# mainPCB.net
KiCad netlist of a schematic drawn in EAGLE
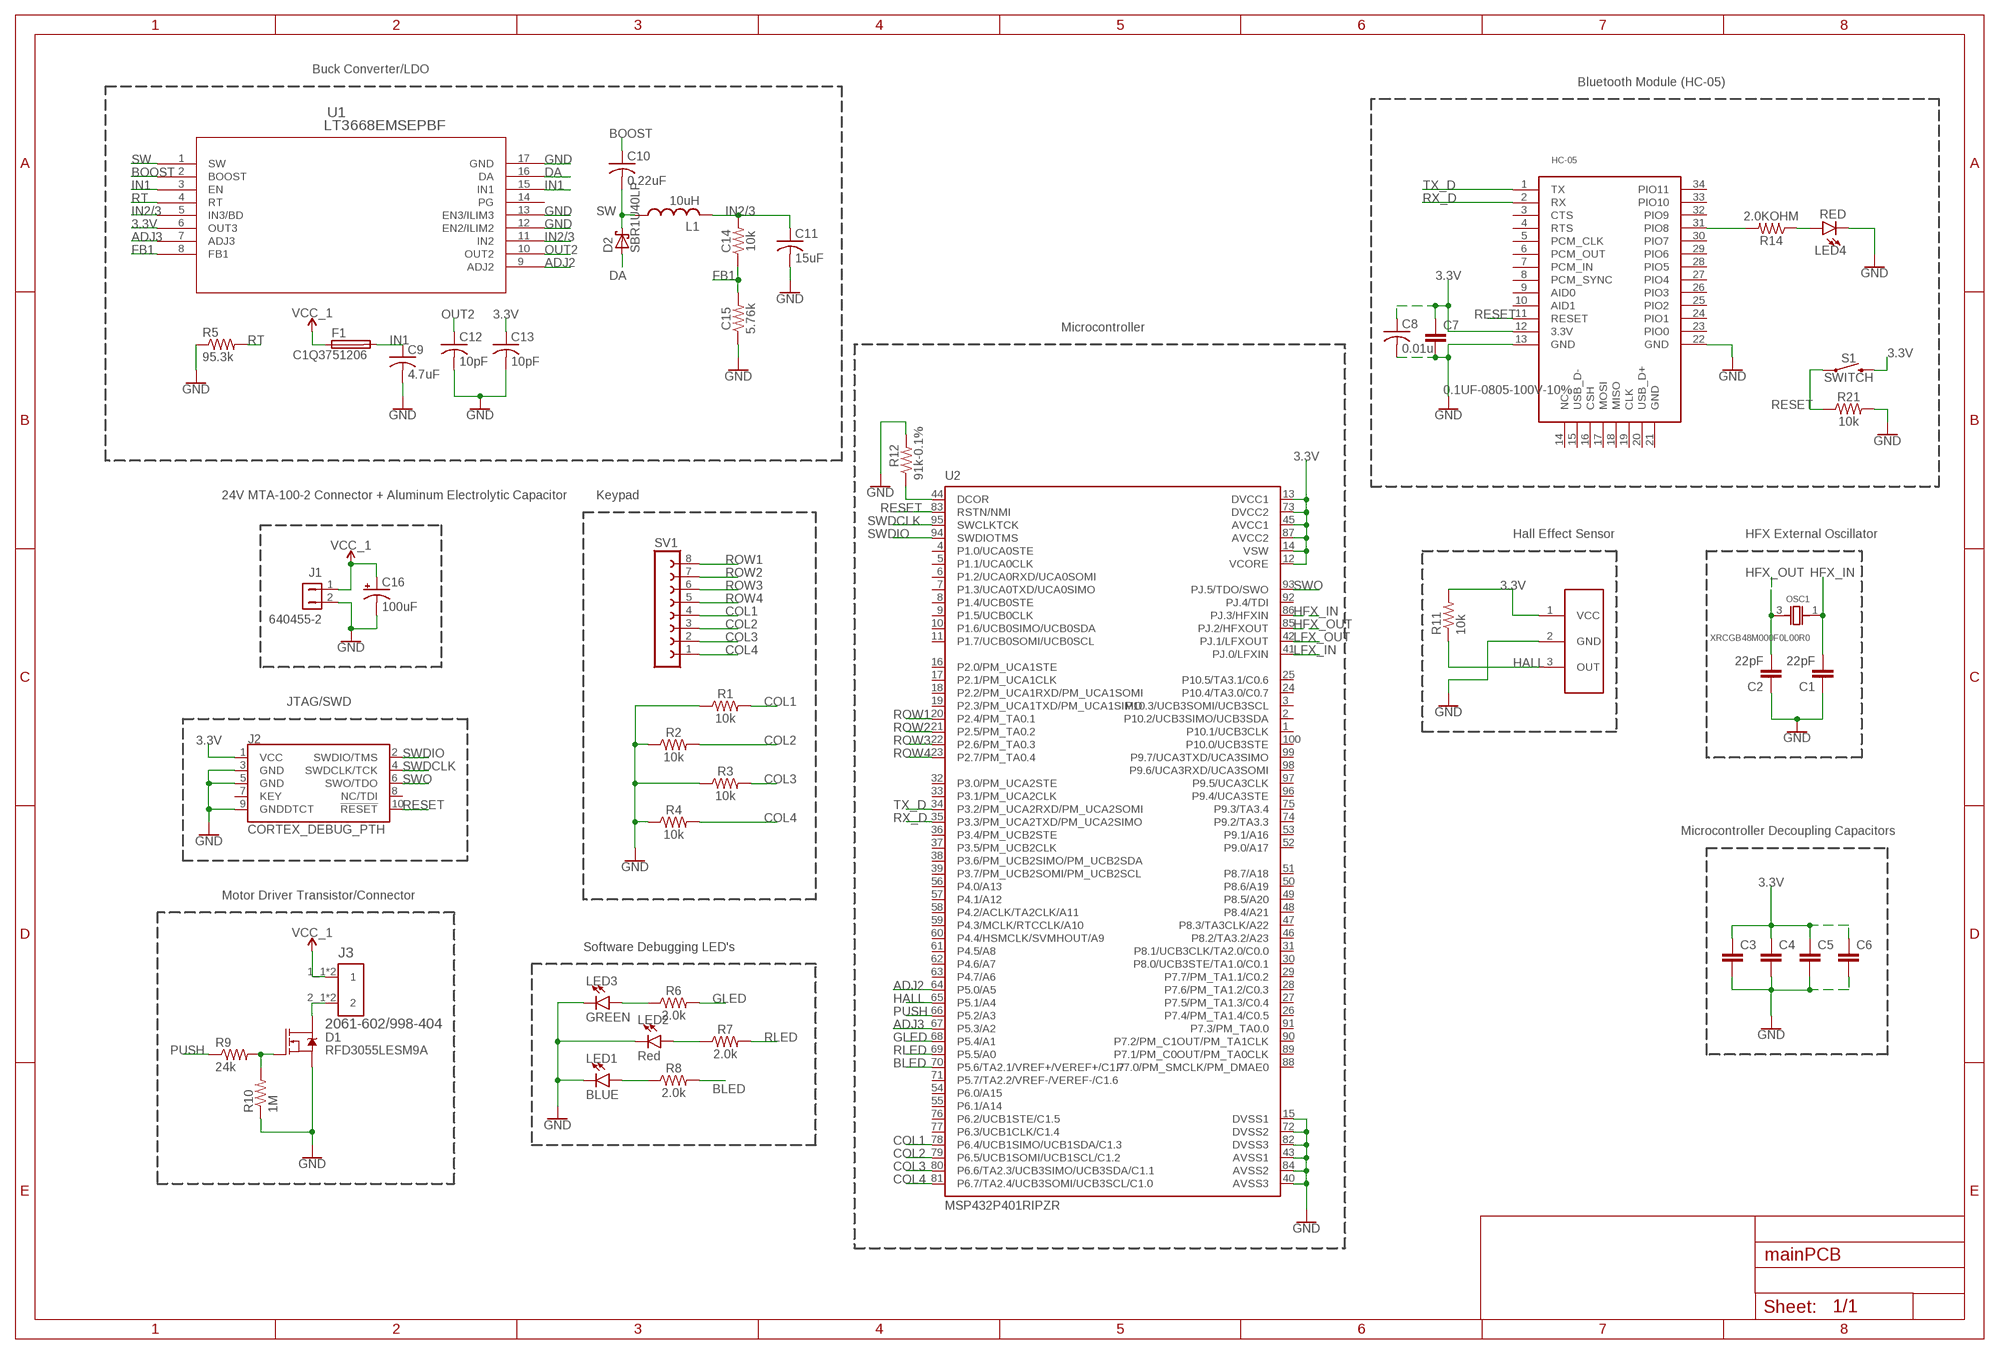
[diagram p0: schematic, sheet 1]

(export (version "E")
  (design (tool "Eeschema 10.0.6"))
  (components
    (comp (ref "C1")
      (value "22pF")
      (footprint "eagle-import:0603")
      (libsource (lib "eagle-import") (part "22PF-0603-50V-5%"))
    )
    (comp (ref "C2")
      (value "22pF")
      (footprint "eagle-import:0603")
      (libsource (lib "eagle-import") (part "22PF-0603-50V-5%"))
    )
    (comp (ref "C3")
      (value "0.1UF-0805-100V-10%")
      (footprint "eagle-import:0805")
      (libsource (lib "eagle-import") (part "0.1UF-0805-100V-10%"))
    )
    (comp (ref "C4")
      (value "0.1UF-0805-100V-10%")
      (footprint "eagle-import:0805")
      (libsource (lib "eagle-import") (part "0.1UF-0805-100V-10%"))
    )
    (comp (ref "C5")
      (value "0.1UF-0805-100V-10%")
      (footprint "eagle-import:0805")
      (libsource (lib "eagle-import") (part "0.1UF-0805-100V-10%"))
    )
    (comp (ref "C6")
      (value "0.1UF-0805-100V-10%")
      (footprint "eagle-import:0805")
      (libsource (lib "eagle-import") (part "0.1UF-0805-100V-10%"))
    )
    (comp (ref "C7")
      (value "0.1UF-0805-100V-10%")
      (footprint "eagle-import:0805")
      (libsource (lib "eagle-import") (part "0.1UF-0805-100V-10%"))
    )
    (comp (ref "C8")
      (value "0.01u")
      (footprint "eagle-import:C0805")
      (libsource (lib "eagle-import") (part "C-USC0805"))
    )
    (comp (ref "C9")
      (value "4.7uF")
      (footprint "eagle-import:C0805")
      (libsource (lib "eagle-import") (part "C-USC0805"))
    )
    (comp (ref "C10")
      (value "0.22uF")
      (footprint "eagle-import:C0805")
      (libsource (lib "eagle-import") (part "C-USC0805"))
    )
    (comp (ref "C11")
      (value "15uF")
      (footprint "eagle-import:C0805")
      (libsource (lib "eagle-import") (part "C-USC0805"))
    )
    (comp (ref "C12")
      (value "10pF")
      (footprint "eagle-import:C0805")
      (libsource (lib "eagle-import") (part "C-USC0805"))
    )
    (comp (ref "C13")
      (value "10pF")
      (footprint "eagle-import:C0805")
      (libsource (lib "eagle-import") (part "C-USC0805"))
    )
    (comp (ref "C14")
      (value "10k")
      (footprint "eagle-import:R0805")
      (libsource (lib "eagle-import") (part "ERJ-PB6"))
    )
    (comp (ref "C15")
      (value "5.76k")
      (footprint "eagle-import:R0805")
      (libsource (lib "eagle-import") (part "ERJ-PB6"))
    )
    (comp (ref "C16")
      (value "100uF")
      (footprint "eagle-import:PANASONIC_D")
      (libsource (lib "eagle-import") (part "EEE-1HA101UP"))
    )
    (comp (ref "D1")
      (value "RFD3055LESM9A")
      (footprint "eagle-import:DPAK229P990X239-4N")
      (libsource (lib "eagle-import") (part "RFD3055LESM9A"))
    )
    (comp (ref "D2")
      (value "SBR1U40LP")
      (footprint "eagle-import:3-XDFN")
      (libsource (lib "eagle-import") (part "SBR1U40LP"))
    )
    (comp (ref "F1")
      (value "C1Q3751206")
      (footprint "eagle-import:C1206")
      (libsource (lib "eagle-import") (part "C1Q3751206"))
    )
    (comp (ref "H1")
      (value "HES")
      (footprint "eagle-import:SIP3-UA")
      (libsource (lib "eagle-import") (part "AH1807-P-B"))
    )
    (comp (ref "HC-05")
      (value "HC-05")
      (footprint "eagle-import:XCVR_HC-05")
      (libsource (lib "eagle-import") (part "HC-05HC-05"))
    )
    (comp (ref "J1")
      (value "640455-2")
      (footprint "eagle-import:2-PIN_CONNECTOR")
      (fields (field (name "MF") "TE Connectivity"))
      (libsource (lib "eagle-import") (part "640455-2"))
    )
    (comp (ref "J2")
      (value "CORTEX_DEBUG_PTH")
      (footprint "eagle-import:2X5-PTH-1.27MM")
      (libsource (lib "eagle-import") (part "CORTEX_DEBUG_PTH"))
    )
    (comp (ref "J3")
      (value "2061-602/998-404")
      (footprint "eagle-import:WAGO_2061-602_998-404")
      (fields (field (name "MF") "WAGO"))
      (libsource (lib "eagle-import") (part "2061-602/998-404"))
    )
    (comp (ref "L1")
      (value "10uH")
      (footprint "eagle-import:L3225M")
      (libsource (lib "eagle-import") (part "CBC3225T150KR1210"))
    )
    (comp (ref "LED1")
      (value "BLUE")
      (footprint "eagle-import:LED-0603")
      (libsource (lib "eagle-import") (part "LED-BLUE0603"))
    )
    (comp (ref "LED2")
      (value "Red")
      (footprint "eagle-import:LED-0603")
      (libsource (lib "eagle-import") (part "LED-RED0603-SMART"))
    )
    (comp (ref "LED3")
      (value "GREEN")
      (footprint "eagle-import:LED-0603")
      (libsource (lib "eagle-import") (part "LED-GREEN0603"))
    )
    (comp (ref "LED4")
      (value "RED")
      (footprint "eagle-import:LED-0603")
      (libsource (lib "eagle-import") (part "LED-RED0603"))
    )
    (comp (ref "OSC1")
      (value "XRCGB48M000F0L00R0")
      (footprint "eagle-import:XTAL_XRCGB24M000F0L00R0")
      (libsource (lib "eagle-import") (part "XRCGB48M000F0L00R0"))
    )
    (comp (ref "R1")
      (value "10k")
      (footprint "eagle-import:0805")
      (libsource (lib "eagle-import") (part "10KOHM-0805-1/4W-1%"))
    )
    (comp (ref "R2")
      (value "10k")
      (footprint "eagle-import:0805")
      (libsource (lib "eagle-import") (part "10KOHM-0805-1/4W-1%"))
    )
    (comp (ref "R3")
      (value "10k")
      (footprint "eagle-import:0805")
      (libsource (lib "eagle-import") (part "10KOHM-0805-1/4W-1%"))
    )
    (comp (ref "R4")
      (value "10k")
      (footprint "eagle-import:0805")
      (libsource (lib "eagle-import") (part "10KOHM-0805-1/4W-1%"))
    )
    (comp (ref "R5")
      (value "95.3k")
      (footprint "eagle-import:R0805")
      (libsource (lib "eagle-import") (part "R-US_R0805"))
    )
    (comp (ref "R6")
      (value "2.0k")
      (footprint "eagle-import:0603")
      (libsource (lib "eagle-import") (part "2.0KOHM-0603-1/10W-5%"))
    )
    (comp (ref "R7")
      (value "2.0k")
      (footprint "eagle-import:0603")
      (libsource (lib "eagle-import") (part "2.0KOHM-0603-1/10W-5%"))
    )
    (comp (ref "R8")
      (value "2.0k")
      (footprint "eagle-import:0603")
      (libsource (lib "eagle-import") (part "2.0KOHM-0603-1/10W-5%"))
    )
    (comp (ref "R9")
      (value "24k")
      (footprint "eagle-import:R0805")
      (libsource (lib "eagle-import") (part "R-US_R0805"))
    )
    (comp (ref "R10")
      (value "1M")
      (footprint "eagle-import:R0805")
      (libsource (lib "eagle-import") (part "R-US_R0805"))
    )
    (comp (ref "R11")
      (value "10k")
      (footprint "eagle-import:R0805")
      (libsource (lib "eagle-import") (part "R-US_R0805"))
    )
    (comp (ref "R12")
      (value "91k-0.1%")
      (footprint "eagle-import:R0805")
      (libsource (lib "eagle-import") (part "R-US_R0805"))
    )
    (comp (ref "R14")
      (value "2.0KOHM")
      (footprint "eagle-import:0805")
      (libsource (lib "eagle-import") (part "2.0KOHM"))
    )
    (comp (ref "R21")
      (value "10k")
      (footprint "eagle-import:0805")
      (libsource (lib "eagle-import") (part "10KOHM-0805-1/4W-1%"))
    )
    (comp (ref "S1")
      (value "SWITCH")
      (footprint "eagle-import:TACTILE_SWITCH_SMD_5.2MM")
      (libsource (lib "eagle-import") (part "MOMENTARY-SWITCH-SPST-SMD-5.2-REDUNDANT"))
    )
    (comp (ref "SV1")
      (value "FE08-1")
      (footprint "eagle-import:FE08")
      (libsource (lib "eagle-import") (part "FE08-1"))
    )
    (comp (ref "U1")
      (value "LT3668EMSEPBF")
      (footprint "eagle-import:MSOP-16_MSE")
      (fields
        (field (name "DIGI-KEY_PART_NUMBER") "LT3668EMSE#PBF-ND")
        (field (name "MF") "Linear Technology")
        (field (name "MP") "LT3668EMSE#PBF")
      )
      (libsource (lib "eagle-import") (part "LT3668EMSEPBF"))
    )
    (comp (ref "U2")
      (value "MSP432P401RIPZR")
      (footprint "eagle-import:QFP50P1600X1600X160-100N")
      (fields (field (name "MF") "Texas Instruments"))
      (libsource (lib "eagle-import") (part "MSP432P401RIPZR"))
    )
  )
  (nets
    (net (code "1") (name "/3.3V") (class "Default")
      (node (ref "C13") (pin "1") (pinfunction "1_1") (pintype "passive"))
      (node (ref "C3") (pin "1") (pinfunction "1_1") (pintype "passive"))
      (node (ref "C4") (pin "1") (pinfunction "1_1") (pintype "passive"))
      (node (ref "C5") (pin "1") (pinfunction "1_1") (pintype "passive"))
      (node (ref "C6") (pin "1") (pinfunction "1_1") (pintype "passive"))
      (node (ref "C7") (pin "1") (pinfunction "1_1") (pintype "passive"))
      (node (ref "C8") (pin "1") (pinfunction "1_1") (pintype "passive"))
      (node (ref "H1") (pin "1") (pinfunction "VCC_1") (pintype "bidirectional"))
      (node (ref "HC-05") (pin "12") (pinfunction "3.3V_12") (pintype "bidirectional"))
      (node (ref "J2") (pin "1") (pinfunction "VCC_1") (pintype "bidirectional"))
      (node (ref "R11") (pin "2") (pinfunction "2_2") (pintype "passive"))
      (node (ref "S1") (pin "3") (pinfunction "2_3") (pintype "passive"))
      (node (ref "S1") (pin "4") (pinfunction "2_4") (pintype "passive"))
      (node (ref "U1") (pin "6") (pinfunction "OUT3_6") (pintype "output"))
      (node (ref "U2") (pin "12") (pinfunction "VCORE_12") (pintype "power_in"))
      (node (ref "U2") (pin "13") (pinfunction "DVCC1_13") (pintype "power_in"))
      (node (ref "U2") (pin "14") (pinfunction "VSW_14") (pintype "power_in"))
      (node (ref "U2") (pin "45") (pinfunction "AVCC1_45") (pintype "power_in"))
      (node (ref "U2") (pin "73") (pinfunction "DVCC2_73") (pintype "power_in"))
      (node (ref "U2") (pin "87") (pinfunction "AVCC2_87") (pintype "power_in"))
    )
    (net (code "2") (name "/ADJ2") (class "Default")
      (node (ref "U1") (pin "9") (pinfunction "ADJ2_9") (pintype "output"))
      (node (ref "U2") (pin "64") (pinfunction "P5.0/A5_64") (pintype "bidirectional"))
    )
    (net (code "3") (name "/ADJ3") (class "Default")
      (node (ref "U1") (pin "7") (pinfunction "ADJ3_7") (pintype "output"))
      (node (ref "U2") (pin "67") (pinfunction "P5.3/A2_67") (pintype "bidirectional"))
    )
    (net (code "4") (name "/BLED") (class "Default")
      (node (ref "R8") (pin "2") (pinfunction "2_2") (pintype "passive"))
      (node (ref "U2") (pin "70") (pinfunction "P5.6/TA2.1/VREF+/VEREF+/C1.7_70") (pintype "bidirectional"))
    )
    (net (code "5") (name "/BOOST") (class "Default")
      (node (ref "C10") (pin "1") (pinfunction "1_1") (pintype "passive"))
      (node (ref "U1") (pin "2") (pinfunction "BOOST_2") (pintype "input"))
    )
    (net (code "6") (name "/COL1") (class "Default")
      (node (ref "R1") (pin "2") (pinfunction "2_2") (pintype "passive"))
      (node (ref "SV1") (pin "4") (pinfunction "4_4") (pintype "passive"))
      (node (ref "U2") (pin "78") (pinfunction "P6.4/UCB1SIMO/UCB1SDA/C1.3_78") (pintype "bidirectional"))
    )
    (net (code "7") (name "/COL2") (class "Default")
      (node (ref "R2") (pin "2") (pinfunction "2_2") (pintype "passive"))
      (node (ref "SV1") (pin "3") (pinfunction "3_3") (pintype "passive"))
      (node (ref "U2") (pin "79") (pinfunction "P6.5/UCB1SOMI/UCB1SCL/C1.2_79") (pintype "bidirectional"))
    )
    (net (code "8") (name "/COL3") (class "Default")
      (node (ref "R3") (pin "2") (pinfunction "2_2") (pintype "passive"))
      (node (ref "SV1") (pin "2") (pinfunction "2_2") (pintype "passive"))
      (node (ref "U2") (pin "80") (pinfunction "P6.6/TA2.3/UCB3SIMO/UCB3SDA/C1.1_80") (pintype "bidirectional"))
    )
    (net (code "9") (name "/COL4") (class "Default")
      (node (ref "R4") (pin "2") (pinfunction "2_2") (pintype "passive"))
      (node (ref "SV1") (pin "1") (pinfunction "1_1") (pintype "passive"))
      (node (ref "U2") (pin "81") (pinfunction "P6.7/TA2.4/UCB3SOMI/UCB3SCL/C1.0_81") (pintype "bidirectional"))
    )
    (net (code "10") (name "/DA") (class "Default")
      (node (ref "D2") (pin "1") (pinfunction "A_1") (pintype "passive"))
      (node (ref "U1") (pin "16") (pinfunction "DA_16") (pintype "passive"))
    )
    (net (code "11") (name "/FB1") (class "Default")
      (node (ref "C14") (pin "1") (pinfunction "1_1") (pintype "passive"))
      (node (ref "C15") (pin "2") (pinfunction "2_2") (pintype "passive"))
      (node (ref "U1") (pin "8") (pinfunction "FB1_8") (pintype "passive"))
    )
    (net (code "12") (name "/GLED") (class "Default")
      (node (ref "R6") (pin "2") (pinfunction "2_2") (pintype "passive"))
      (node (ref "U2") (pin "68") (pinfunction "P5.4/A1_68") (pintype "bidirectional"))
    )
    (net (code "13") (name "/HALL") (class "Default")
      (node (ref "H1") (pin "3") (pinfunction "OUT_3") (pintype "bidirectional"))
      (node (ref "R11") (pin "1") (pinfunction "1_1") (pintype "passive"))
      (node (ref "U2") (pin "65") (pinfunction "P5.1/A4_65") (pintype "bidirectional"))
    )
    (net (code "14") (name "/HFX_IN") (class "Default")
      (node (ref "C1") (pin "2") (pinfunction "2_2") (pintype "passive"))
      (node (ref "OSC1") (pin "1") (pinfunction "1_1") (pintype "passive"))
      (node (ref "U2") (pin "86") (pinfunction "PJ.3/HFXIN_86") (pintype "bidirectional"))
    )
    (net (code "15") (name "/HFX_OUT") (class "Default")
      (node (ref "C2") (pin "2") (pinfunction "2_2") (pintype "passive"))
      (node (ref "OSC1") (pin "3") (pinfunction "2_3") (pintype "passive"))
      (node (ref "U2") (pin "85") (pinfunction "PJ.2/HFXOUT_85") (pintype "bidirectional"))
    )
    (net (code "16") (name "/IN1") (class "Default")
      (node (ref "C9") (pin "1") (pinfunction "1_1") (pintype "passive"))
      (node (ref "F1") (pin "2") (pinfunction "2_2") (pintype "passive"))
      (node (ref "U1") (pin "15") (pinfunction "IN1_15") (pintype "input"))
      (node (ref "U1") (pin "3") (pinfunction "EN_3") (pintype "passive"))
    )
    (net (code "17") (name "/IN2{slash}3") (class "Default")
      (node (ref "C11") (pin "1") (pinfunction "1_1") (pintype "passive"))
      (node (ref "C14") (pin "2") (pinfunction "2_2") (pintype "passive"))
      (node (ref "L1") (pin "2") (pinfunction "2_2") (pintype "passive"))
      (node (ref "U1") (pin "11") (pinfunction "IN2_11") (pintype "input"))
      (node (ref "U1") (pin "5") (pinfunction "IN3/BD_5") (pintype "input"))
    )
    (net (code "18") (name "/LFX_IN") (class "Default")
      (node (ref "U2") (pin "41") (pinfunction "PJ.0/LFXIN_41") (pintype "bidirectional"))
    )
    (net (code "19") (name "/LFX_OUT") (class "Default")
      (node (ref "U2") (pin "42") (pinfunction "PJ.1/LFXOUT_42") (pintype "bidirectional"))
    )
    (net (code "20") (name "/OUT2") (class "Default")
      (node (ref "C12") (pin "1") (pinfunction "1_1") (pintype "passive"))
      (node (ref "U1") (pin "10") (pinfunction "OUT2_10") (pintype "output"))
    )
    (net (code "21") (name "/PUSH") (class "Default")
      (node (ref "R9") (pin "1") (pinfunction "1_1") (pintype "passive"))
      (node (ref "U2") (pin "66") (pinfunction "P5.2/A3_66") (pintype "bidirectional"))
    )
    (net (code "22") (name "/RESET") (class "Default")
      (node (ref "HC-05") (pin "11") (pinfunction "RESET_11") (pintype "bidirectional"))
      (node (ref "J2") (pin "10") (pinfunction "~{RESET}_10") (pintype "bidirectional"))
      (node (ref "R21") (pin "1") (pinfunction "1_1") (pintype "passive"))
      (node (ref "S1") (pin "1") (pinfunction "1_1") (pintype "passive"))
      (node (ref "S1") (pin "2") (pinfunction "1_2") (pintype "passive"))
      (node (ref "U2") (pin "83") (pinfunction "RSTN/NMI_83") (pintype "bidirectional"))
    )
    (net (code "23") (name "/RLED") (class "Default")
      (node (ref "R7") (pin "2") (pinfunction "2_2") (pintype "passive"))
      (node (ref "U2") (pin "69") (pinfunction "P5.5/A0_69") (pintype "bidirectional"))
    )
    (net (code "24") (name "/ROW1") (class "Default")
      (node (ref "SV1") (pin "8") (pinfunction "8_8") (pintype "passive"))
      (node (ref "U2") (pin "20") (pinfunction "P2.4/PM_TA0.1_20") (pintype "bidirectional"))
    )
    (net (code "25") (name "/ROW2") (class "Default")
      (node (ref "SV1") (pin "7") (pinfunction "7_7") (pintype "passive"))
      (node (ref "U2") (pin "21") (pinfunction "P2.5/PM_TA0.2_21") (pintype "bidirectional"))
    )
    (net (code "26") (name "/ROW3") (class "Default")
      (node (ref "SV1") (pin "6") (pinfunction "6_6") (pintype "passive"))
      (node (ref "U2") (pin "22") (pinfunction "P2.6/PM_TA0.3_22") (pintype "bidirectional"))
    )
    (net (code "27") (name "/ROW4") (class "Default")
      (node (ref "SV1") (pin "5") (pinfunction "5_5") (pintype "passive"))
      (node (ref "U2") (pin "23") (pinfunction "P2.7/PM_TA0.4_23") (pintype "bidirectional"))
    )
    (net (code "28") (name "/RT") (class "Default")
      (node (ref "R5") (pin "2") (pinfunction "2_2") (pintype "passive"))
      (node (ref "U1") (pin "4") (pinfunction "RT_4") (pintype "input"))
    )
    (net (code "29") (name "/RX_D") (class "Default")
      (node (ref "HC-05") (pin "2") (pinfunction "RX_2") (pintype "bidirectional"))
      (node (ref "U2") (pin "35") (pinfunction "P3.3/PM_UCA2TXD/PM_UCA2SIMO_35") (pintype "bidirectional"))
    )
    (net (code "30") (name "/SW") (class "Default")
      (node (ref "C10") (pin "2") (pinfunction "2_2") (pintype "passive"))
      (node (ref "D2") (pin "2") (pinfunction "C_2") (pintype "passive"))
      (node (ref "D2") (pin "3") (pinfunction "C_3") (pintype "passive"))
      (node (ref "L1") (pin "1") (pinfunction "1_1") (pintype "passive"))
      (node (ref "U1") (pin "1") (pinfunction "SW_1") (pintype "output"))
    )
    (net (code "31") (name "/SWDCLK") (class "Default")
      (node (ref "J2") (pin "4") (pinfunction "SWDCLK/TCK_4") (pintype "bidirectional"))
      (node (ref "U2") (pin "95") (pinfunction "SWCLKTCK_95") (pintype "bidirectional"))
    )
    (net (code "32") (name "/SWDIO") (class "Default")
      (node (ref "J2") (pin "2") (pinfunction "SWDIO/TMS_2") (pintype "bidirectional"))
      (node (ref "U2") (pin "94") (pinfunction "SWDIOTMS_94") (pintype "bidirectional"))
    )
    (net (code "33") (name "/SWO") (class "Default")
      (node (ref "J2") (pin "6") (pinfunction "SWO/TDO_6") (pintype "bidirectional"))
      (node (ref "U2") (pin "93") (pinfunction "PJ.5/TDO/SWO_93") (pintype "bidirectional"))
    )
    (net (code "34") (name "/TX_D") (class "Default")
      (node (ref "HC-05") (pin "1") (pinfunction "TX_1") (pintype "bidirectional"))
      (node (ref "U2") (pin "34") (pinfunction "P3.2/PM_UCA2RXD/PM_UCA2SOMI_34") (pintype "bidirectional"))
    )
    (net (code "35") (name "GND") (class "Default")
      (node (ref "C1") (pin "1") (pinfunction "1_1") (pintype "passive"))
      (node (ref "C11") (pin "2") (pinfunction "2_2") (pintype "passive"))
      (node (ref "C12") (pin "2") (pinfunction "2_2") (pintype "passive"))
      (node (ref "C13") (pin "2") (pinfunction "2_2") (pintype "passive"))
      (node (ref "C15") (pin "1") (pinfunction "1_1") (pintype "passive"))
      (node (ref "C16") (pin "-") (pinfunction "-_-") (pintype "passive"))
      (node (ref "C2") (pin "1") (pinfunction "1_1") (pintype "passive"))
      (node (ref "C3") (pin "2") (pinfunction "2_2") (pintype "passive"))
      (node (ref "C4") (pin "2") (pinfunction "2_2") (pintype "passive"))
      (node (ref "C5") (pin "2") (pinfunction "2_2") (pintype "passive"))
      (node (ref "C6") (pin "2") (pinfunction "2_2") (pintype "passive"))
      (node (ref "C7") (pin "2") (pinfunction "2_2") (pintype "passive"))
      (node (ref "C8") (pin "2") (pinfunction "2_2") (pintype "passive"))
      (node (ref "C9") (pin "2") (pinfunction "2_2") (pintype "passive"))
      (node (ref "D1") (pin "3") (pinfunction "S_3") (pintype "bidirectional"))
      (node (ref "H1") (pin "2") (pinfunction "GND_2") (pintype "bidirectional"))
      (node (ref "HC-05") (pin "13") (pinfunction "GND_13") (pintype "bidirectional"))
      (node (ref "HC-05") (pin "22") (pinfunction "GND_22") (pintype "bidirectional"))
      (node (ref "J1") (pin "2") (pinfunction "2_2") (pintype "passive"))
      (node (ref "J2") (pin "3") (pinfunction "GND_3") (pintype "bidirectional"))
      (node (ref "J2") (pin "5") (pinfunction "GND_5") (pintype "bidirectional"))
      (node (ref "J2") (pin "9") (pinfunction "GNDDTCT_9") (pintype "bidirectional"))
      (node (ref "LED1") (pin "C") (pinfunction "C_C") (pintype "passive"))
      (node (ref "LED2") (pin "C") (pinfunction "C_C") (pintype "passive"))
      (node (ref "LED3") (pin "C") (pinfunction "C_C") (pintype "passive"))
      (node (ref "LED4") (pin "C") (pinfunction "C_C") (pintype "passive"))
      (node (ref "R1") (pin "1") (pinfunction "1_1") (pintype "passive"))
      (node (ref "R10") (pin "1") (pinfunction "1_1") (pintype "passive"))
      (node (ref "R12") (pin "2") (pinfunction "2_2") (pintype "passive"))
      (node (ref "R2") (pin "1") (pinfunction "1_1") (pintype "passive"))
      (node (ref "R21") (pin "2") (pinfunction "2_2") (pintype "passive"))
      (node (ref "R3") (pin "1") (pinfunction "1_1") (pintype "passive"))
      (node (ref "R4") (pin "1") (pinfunction "1_1") (pintype "passive"))
      (node (ref "R5") (pin "1") (pinfunction "1_1") (pintype "passive"))
      (node (ref "U1") (pin "12") (pinfunction "EN2/ILIM2_12") (pintype "passive"))
      (node (ref "U1") (pin "13") (pinfunction "EN3/ILIM3_13") (pintype "passive"))
      (node (ref "U1") (pin "17") (pinfunction "GND_17") (pintype "power_in"))
      (node (ref "U2") (pin "15") (pinfunction "DVSS1_15") (pintype "power_in"))
      (node (ref "U2") (pin "40") (pinfunction "AVSS3_40") (pintype "power_in"))
      (node (ref "U2") (pin "43") (pinfunction "AVSS1_43") (pintype "power_in"))
      (node (ref "U2") (pin "72") (pinfunction "DVSS2_72") (pintype "power_in"))
      (node (ref "U2") (pin "82") (pinfunction "DVSS3_82") (pintype "power_in"))
      (node (ref "U2") (pin "84") (pinfunction "AVSS2_84") (pintype "power_in"))
    )
    (net (code "36") (name "Net-(D1-D)") (class "Default")
      (node (ref "D1") (pin "4") (pinfunction "D_4") (pintype "bidirectional"))
      (node (ref "J3") (pin "2_1") (pinfunction "2_2_1") (pintype "passive"))
      (node (ref "J3") (pin "2_2") (pinfunction "2_2_2") (pintype "passive"))
    )
    (net (code "37") (name "Net-(D1-G)") (class "Default")
      (node (ref "D1") (pin "1") (pinfunction "G_1") (pintype "bidirectional"))
      (node (ref "R10") (pin "2") (pinfunction "2_2") (pintype "passive"))
      (node (ref "R9") (pin "2") (pinfunction "2_2") (pintype "passive"))
    )
    (net (code "38") (name "Net-(HC-05-PIO8)") (class "Default")
      (node (ref "HC-05") (pin "31") (pinfunction "PIO8_31") (pintype "bidirectional"))
      (node (ref "R14") (pin "2") (pinfunction "2_2") (pintype "passive"))
    )
    (net (code "39") (name "Net-(LED1-PadA)") (class "Default")
      (node (ref "LED1") (pin "A") (pinfunction "A_A") (pintype "passive"))
      (node (ref "R8") (pin "1") (pinfunction "1_1") (pintype "passive"))
    )
    (net (code "40") (name "Net-(LED2-PadA)") (class "Default")
      (node (ref "LED2") (pin "A") (pinfunction "A_A") (pintype "passive"))
      (node (ref "R7") (pin "1") (pinfunction "1_1") (pintype "passive"))
    )
    (net (code "41") (name "Net-(LED3-PadA)") (class "Default")
      (node (ref "LED3") (pin "A") (pinfunction "A_A") (pintype "passive"))
      (node (ref "R6") (pin "1") (pinfunction "1_1") (pintype "passive"))
    )
    (net (code "42") (name "Net-(LED4-PadA)") (class "Default")
      (node (ref "LED4") (pin "A") (pinfunction "A_A") (pintype "passive"))
      (node (ref "R14") (pin "1") (pinfunction "1_1") (pintype "passive"))
    )
    (net (code "43") (name "Net-(U2-DCOR)") (class "Default")
      (node (ref "R12") (pin "1") (pinfunction "1_1") (pintype "passive"))
      (node (ref "U2") (pin "44") (pinfunction "DCOR_44") (pintype "input"))
    )
    (net (code "44") (name "VCC_1") (class "Default")
      (node (ref "C16") (pin "+") (pinfunction "+_+") (pintype "passive"))
      (node (ref "F1") (pin "1") (pinfunction "1_1") (pintype "passive"))
      (node (ref "J1") (pin "1") (pinfunction "1_1") (pintype "passive"))
      (node (ref "J3") (pin "1_1") (pinfunction "1_1_1") (pintype "passive"))
      (node (ref "J3") (pin "1_2") (pinfunction "1_1_2") (pintype "passive"))
    )
    (net (code "45") (name "unconnected-(HC-05-AID0-Pad9)") (class "Default")
      (node (ref "HC-05") (pin "9") (pinfunction "AID0_9") (pintype "bidirectional"))
    )
    (net (code "46") (name "unconnected-(HC-05-AID1-Pad10)") (class "Default")
      (node (ref "HC-05") (pin "10") (pinfunction "AID1_10") (pintype "bidirectional"))
    )
    (net (code "47") (name "unconnected-(HC-05-CLK-Pad19)") (class "Default")
      (node (ref "HC-05") (pin "19") (pinfunction "CLK_19") (pintype "bidirectional"))
    )
    (net (code "48") (name "unconnected-(HC-05-CSH-Pad16)") (class "Default")
      (node (ref "HC-05") (pin "16") (pinfunction "CSH_16") (pintype "bidirectional"))
    )
    (net (code "49") (name "unconnected-(HC-05-CTS-Pad3)") (class "Default")
      (node (ref "HC-05") (pin "3") (pinfunction "CTS_3") (pintype "bidirectional"))
    )
    (net (code "50") (name "unconnected-(HC-05-GND-Pad21)") (class "Default")
      (node (ref "HC-05") (pin "21") (pinfunction "GND_21") (pintype "bidirectional"))
    )
    (net (code "51") (name "unconnected-(HC-05-MISO-Pad18)") (class "Default")
      (node (ref "HC-05") (pin "18") (pinfunction "MISO_18") (pintype "bidirectional"))
    )
    (net (code "52") (name "unconnected-(HC-05-MOSI-Pad17)") (class "Default")
      (node (ref "HC-05") (pin "17") (pinfunction "MOSI_17") (pintype "bidirectional"))
    )
    (net (code "53") (name "unconnected-(HC-05-NC-Pad14)") (class "Default")
      (node (ref "HC-05") (pin "14") (pinfunction "NC_14") (pintype "bidirectional"))
    )
    (net (code "54") (name "unconnected-(HC-05-PCM_CLK-Pad5)") (class "Default")
      (node (ref "HC-05") (pin "5") (pinfunction "PCM_CLK_5") (pintype "bidirectional"))
    )
    (net (code "55") (name "unconnected-(HC-05-PCM_IN-Pad7)") (class "Default")
      (node (ref "HC-05") (pin "7") (pinfunction "PCM_IN_7") (pintype "bidirectional"))
    )
    (net (code "56") (name "unconnected-(HC-05-PCM_OUT-Pad6)") (class "Default")
      (node (ref "HC-05") (pin "6") (pinfunction "PCM_OUT_6") (pintype "bidirectional"))
    )
    (net (code "57") (name "unconnected-(HC-05-PCM_SYNC-Pad8)") (class "Default")
      (node (ref "HC-05") (pin "8") (pinfunction "PCM_SYNC_8") (pintype "bidirectional"))
    )
    (net (code "58") (name "unconnected-(HC-05-PIO0-Pad23)") (class "Default")
      (node (ref "HC-05") (pin "23") (pinfunction "PIO0_23") (pintype "bidirectional"))
    )
    (net (code "59") (name "unconnected-(HC-05-PIO1-Pad24)") (class "Default")
      (node (ref "HC-05") (pin "24") (pinfunction "PIO1_24") (pintype "bidirectional"))
    )
    (net (code "60") (name "unconnected-(HC-05-PIO2-Pad25)") (class "Default")
      (node (ref "HC-05") (pin "25") (pinfunction "PIO2_25") (pintype "bidirectional"))
    )
    (net (code "61") (name "unconnected-(HC-05-PIO3-Pad26)") (class "Default")
      (node (ref "HC-05") (pin "26") (pinfunction "PIO3_26") (pintype "bidirectional"))
    )
    (net (code "62") (name "unconnected-(HC-05-PIO4-Pad27)") (class "Default")
      (node (ref "HC-05") (pin "27") (pinfunction "PIO4_27") (pintype "bidirectional"))
    )
    (net (code "63") (name "unconnected-(HC-05-PIO5-Pad28)") (class "Default")
      (node (ref "HC-05") (pin "28") (pinfunction "PIO5_28") (pintype "bidirectional"))
    )
    (net (code "64") (name "unconnected-(HC-05-PIO6-Pad29)") (class "Default")
      (node (ref "HC-05") (pin "29") (pinfunction "PIO6_29") (pintype "bidirectional"))
    )
    (net (code "65") (name "unconnected-(HC-05-PIO7-Pad30)") (class "Default")
      (node (ref "HC-05") (pin "30") (pinfunction "PIO7_30") (pintype "bidirectional"))
    )
    (net (code "66") (name "unconnected-(HC-05-PIO9-Pad32)") (class "Default")
      (node (ref "HC-05") (pin "32") (pinfunction "PIO9_32") (pintype "bidirectional"))
    )
    (net (code "67") (name "unconnected-(HC-05-PIO10-Pad33)") (class "Default")
      (node (ref "HC-05") (pin "33") (pinfunction "PIO10_33") (pintype "bidirectional"))
    )
    (net (code "68") (name "unconnected-(HC-05-PIO11-Pad34)") (class "Default")
      (node (ref "HC-05") (pin "34") (pinfunction "PIO11_34") (pintype "bidirectional"))
    )
    (net (code "69") (name "unconnected-(HC-05-RTS-Pad4)") (class "Default")
      (node (ref "HC-05") (pin "4") (pinfunction "RTS_4") (pintype "bidirectional"))
    )
    (net (code "70") (name "unconnected-(HC-05-USB_D+-Pad20)") (class "Default")
      (node (ref "HC-05") (pin "20") (pinfunction "USB_D+_20") (pintype "bidirectional"))
    )
    (net (code "71") (name "unconnected-(HC-05-USB_D--Pad15)") (class "Default")
      (node (ref "HC-05") (pin "15") (pinfunction "USB_D-_15") (pintype "bidirectional"))
    )
    (net (code "72") (name "unconnected-(J2-KEY-Pad7)") (class "Default")
      (node (ref "J2") (pin "7") (pinfunction "KEY_7") (pintype "bidirectional"))
    )
    (net (code "73") (name "unconnected-(J2-NC{slash}TDI-Pad8)") (class "Default")
      (node (ref "J2") (pin "8") (pinfunction "NC/TDI_8") (pintype "bidirectional"))
    )
    (net (code "74") (name "unconnected-(U1-PG-Pad14)") (class "Default")
      (node (ref "U1") (pin "14") (pinfunction "PG_14") (pintype "output"))
    )
    (net (code "75") (name "unconnected-(U2-P1.0{slash}UCA0STE-Pad4)") (class "Default")
      (node (ref "U2") (pin "4") (pinfunction "P1.0/UCA0STE_4") (pintype "bidirectional"))
    )
    (net (code "76") (name "unconnected-(U2-P1.1{slash}UCA0CLK-Pad5)") (class "Default")
      (node (ref "U2") (pin "5") (pinfunction "P1.1/UCA0CLK_5") (pintype "bidirectional"))
    )
    (net (code "77") (name "unconnected-(U2-P1.2{slash}UCA0RXD{slash}UCA0SOMI-Pad6)") (class "Default")
      (node (ref "U2") (pin "6") (pinfunction "P1.2/UCA0RXD/UCA0SOMI_6") (pintype "bidirectional"))
    )
    (net (code "78") (name "unconnected-(U2-P1.3{slash}UCA0TXD{slash}UCA0SIMO-Pad7)") (class "Default")
      (node (ref "U2") (pin "7") (pinfunction "P1.3/UCA0TXD/UCA0SIMO_7") (pintype "bidirectional"))
    )
    (net (code "79") (name "unconnected-(U2-P1.4{slash}UCB0STE-Pad8)") (class "Default")
      (node (ref "U2") (pin "8") (pinfunction "P1.4/UCB0STE_8") (pintype "bidirectional"))
    )
    (net (code "80") (name "unconnected-(U2-P1.5{slash}UCB0CLK-Pad9)") (class "Default")
      (node (ref "U2") (pin "9") (pinfunction "P1.5/UCB0CLK_9") (pintype "bidirectional"))
    )
    (net (code "81") (name "unconnected-(U2-P1.6{slash}UCB0SIMO{slash}UCB0SDA-Pad10)") (class "Default")
      (node (ref "U2") (pin "10") (pinfunction "P1.6/UCB0SIMO/UCB0SDA_10") (pintype "bidirectional"))
    )
    (net (code "82") (name "unconnected-(U2-P1.7{slash}UCB0SOMI{slash}UCB0SCL-Pad11)") (class "Default")
      (node (ref "U2") (pin "11") (pinfunction "P1.7/UCB0SOMI/UCB0SCL_11") (pintype "bidirectional"))
    )
    (net (code "83") (name "unconnected-(U2-P2.0{slash}PM_UCA1STE-Pad16)") (class "Default")
      (node (ref "U2") (pin "16") (pinfunction "P2.0/PM_UCA1STE_16") (pintype "bidirectional"))
    )
    (net (code "84") (name "unconnected-(U2-P2.1{slash}PM_UCA1CLK-Pad17)") (class "Default")
      (node (ref "U2") (pin "17") (pinfunction "P2.1/PM_UCA1CLK_17") (pintype "bidirectional"))
    )
    (net (code "85") (name "unconnected-(U2-P2.2{slash}PM_UCA1RXD{slash}PM_UCA1SOMI-Pad18)") (class "Default")
      (node (ref "U2") (pin "18") (pinfunction "P2.2/PM_UCA1RXD/PM_UCA1SOMI_18") (pintype "bidirectional"))
    )
    (net (code "86") (name "unconnected-(U2-P2.3{slash}PM_UCA1TXD{slash}PM_UCA1SIMO-Pad19)") (class "Default")
      (node (ref "U2") (pin "19") (pinfunction "P2.3/PM_UCA1TXD/PM_UCA1SIMO_19") (pintype "bidirectional"))
    )
    (net (code "87") (name "unconnected-(U2-P3.0{slash}PM_UCA2STE-Pad32)") (class "Default")
      (node (ref "U2") (pin "32") (pinfunction "P3.0/PM_UCA2STE_32") (pintype "bidirectional"))
    )
    (net (code "88") (name "unconnected-(U2-P3.1{slash}PM_UCA2CLK-Pad33)") (class "Default")
      (node (ref "U2") (pin "33") (pinfunction "P3.1/PM_UCA2CLK_33") (pintype "bidirectional"))
    )
    (net (code "89") (name "unconnected-(U2-P3.4{slash}PM_UCB2STE-Pad36)") (class "Default")
      (node (ref "U2") (pin "36") (pinfunction "P3.4/PM_UCB2STE_36") (pintype "bidirectional"))
    )
    (net (code "90") (name "unconnected-(U2-P3.5{slash}PM_UCB2CLK-Pad37)") (class "Default")
      (node (ref "U2") (pin "37") (pinfunction "P3.5/PM_UCB2CLK_37") (pintype "bidirectional"))
    )
    (net (code "91") (name "unconnected-(U2-P3.6{slash}PM_UCB2SIMO{slash}PM_UCB2SDA-Pad38)") (class "Default")
      (node (ref "U2") (pin "38") (pinfunction "P3.6/PM_UCB2SIMO/PM_UCB2SDA_38") (pintype "bidirectional"))
    )
    (net (code "92") (name "unconnected-(U2-P3.7{slash}PM_UCB2SOMI{slash}PM_UCB2SCL-Pad39)") (class "Default")
      (node (ref "U2") (pin "39") (pinfunction "P3.7/PM_UCB2SOMI/PM_UCB2SCL_39") (pintype "bidirectional"))
    )
    (net (code "93") (name "unconnected-(U2-P4.0{slash}A13-Pad56)") (class "Default")
      (node (ref "U2") (pin "56") (pinfunction "P4.0/A13_56") (pintype "bidirectional"))
    )
    (net (code "94") (name "unconnected-(U2-P4.1{slash}A12-Pad57)") (class "Default")
      (node (ref "U2") (pin "57") (pinfunction "P4.1/A12_57") (pintype "bidirectional"))
    )
    (net (code "95") (name "unconnected-(U2-P4.2{slash}ACLK{slash}TA2CLK{slash}A11-Pad58)") (class "Default")
      (node (ref "U2") (pin "58") (pinfunction "P4.2/ACLK/TA2CLK/A11_58") (pintype "bidirectional"))
    )
    (net (code "96") (name "unconnected-(U2-P4.3{slash}MCLK{slash}RTCCLK{slash}A10-Pad59)") (class "Default")
      (node (ref "U2") (pin "59") (pinfunction "P4.3/MCLK/RTCCLK/A10_59") (pintype "bidirectional"))
    )
    (net (code "97") (name "unconnected-(U2-P4.4{slash}HSMCLK{slash}SVMHOUT{slash}A9-Pad60)") (class "Default")
      (node (ref "U2") (pin "60") (pinfunction "P4.4/HSMCLK/SVMHOUT/A9_60") (pintype "bidirectional"))
    )
    (net (code "98") (name "unconnected-(U2-P4.5{slash}A8-Pad61)") (class "Default")
      (node (ref "U2") (pin "61") (pinfunction "P4.5/A8_61") (pintype "bidirectional"))
    )
    (net (code "99") (name "unconnected-(U2-P4.6{slash}A7-Pad62)") (class "Default")
      (node (ref "U2") (pin "62") (pinfunction "P4.6/A7_62") (pintype "bidirectional"))
    )
    (net (code "100") (name "unconnected-(U2-P4.7{slash}A6-Pad63)") (class "Default")
      (node (ref "U2") (pin "63") (pinfunction "P4.7/A6_63") (pintype "bidirectional"))
    )
    (net (code "101") (name "unconnected-(U2-P5.7{slash}TA2.2{slash}VREF-{slash}VEREF-{slash}C1.6-Pad71)") (class "Default")
      (node (ref "U2") (pin "71") (pinfunction "P5.7/TA2.2/VREF-/VEREF-/C1.6_71") (pintype "bidirectional"))
    )
    (net (code "102") (name "unconnected-(U2-P6.0{slash}A15-Pad54)") (class "Default")
      (node (ref "U2") (pin "54") (pinfunction "P6.0/A15_54") (pintype "bidirectional"))
    )
    (net (code "103") (name "unconnected-(U2-P6.1{slash}A14-Pad55)") (class "Default")
      (node (ref "U2") (pin "55") (pinfunction "P6.1/A14_55") (pintype "bidirectional"))
    )
    (net (code "104") (name "unconnected-(U2-P6.2{slash}UCB1STE{slash}C1.5-Pad76)") (class "Default")
      (node (ref "U2") (pin "76") (pinfunction "P6.2/UCB1STE/C1.5_76") (pintype "bidirectional"))
    )
    (net (code "105") (name "unconnected-(U2-P6.3{slash}UCB1CLK{slash}C1.4-Pad77)") (class "Default")
      (node (ref "U2") (pin "77") (pinfunction "P6.3/UCB1CLK/C1.4_77") (pintype "bidirectional"))
    )
    (net (code "106") (name "unconnected-(U2-P7.0{slash}PM_SMCLK{slash}PM_DMAE0-Pad88)") (class "Default")
      (node (ref "U2") (pin "88") (pinfunction "P7.0/PM_SMCLK/PM_DMAE0_88") (pintype "bidirectional"))
    )
    (net (code "107") (name "unconnected-(U2-P7.1{slash}PM_C0OUT{slash}PM_TA0CLK-Pad89)") (class "Default")
      (node (ref "U2") (pin "89") (pinfunction "P7.1/PM_C0OUT/PM_TA0CLK_89") (pintype "bidirectional"))
    )
    (net (code "108") (name "unconnected-(U2-P7.2{slash}PM_C1OUT{slash}PM_TA1CLK-Pad90)") (class "Default")
      (node (ref "U2") (pin "90") (pinfunction "P7.2/PM_C1OUT/PM_TA1CLK_90") (pintype "bidirectional"))
    )
    (net (code "109") (name "unconnected-(U2-P7.3{slash}PM_TA0.0-Pad91)") (class "Default")
      (node (ref "U2") (pin "91") (pinfunction "P7.3/PM_TA0.0_91") (pintype "bidirectional"))
    )
    (net (code "110") (name "unconnected-(U2-P7.4{slash}PM_TA1.4{slash}C0.5-Pad26)") (class "Default")
      (node (ref "U2") (pin "26") (pinfunction "P7.4/PM_TA1.4/C0.5_26") (pintype "bidirectional"))
    )
    (net (code "111") (name "unconnected-(U2-P7.5{slash}PM_TA1.3{slash}C0.4-Pad27)") (class "Default")
      (node (ref "U2") (pin "27") (pinfunction "P7.5/PM_TA1.3/C0.4_27") (pintype "bidirectional"))
    )
    (net (code "112") (name "unconnected-(U2-P7.6{slash}PM_TA1.2{slash}C0.3-Pad28)") (class "Default")
      (node (ref "U2") (pin "28") (pinfunction "P7.6/PM_TA1.2/C0.3_28") (pintype "bidirectional"))
    )
    (net (code "113") (name "unconnected-(U2-P7.7{slash}PM_TA1.1{slash}C0.2-Pad29)") (class "Default")
      (node (ref "U2") (pin "29") (pinfunction "P7.7/PM_TA1.1/C0.2_29") (pintype "bidirectional"))
    )
    (net (code "114") (name "unconnected-(U2-P8.0{slash}UCB3STE{slash}TA1.0{slash}C0.1-Pad30)") (class "Default")
      (node (ref "U2") (pin "30") (pinfunction "P8.0/UCB3STE/TA1.0/C0.1_30") (pintype "bidirectional"))
    )
    (net (code "115") (name "unconnected-(U2-P8.1{slash}UCB3CLK{slash}TA2.0{slash}C0.0-Pad31)") (class "Default")
      (node (ref "U2") (pin "31") (pinfunction "P8.1/UCB3CLK/TA2.0/C0.0_31") (pintype "bidirectional"))
    )
    (net (code "116") (name "unconnected-(U2-P8.2{slash}TA3.2{slash}A23-Pad46)") (class "Default")
      (node (ref "U2") (pin "46") (pinfunction "P8.2/TA3.2/A23_46") (pintype "bidirectional"))
    )
    (net (code "117") (name "unconnected-(U2-P8.3{slash}TA3CLK{slash}A22-Pad47)") (class "Default")
      (node (ref "U2") (pin "47") (pinfunction "P8.3/TA3CLK/A22_47") (pintype "bidirectional"))
    )
    (net (code "118") (name "unconnected-(U2-P8.4{slash}A21-Pad48)") (class "Default")
      (node (ref "U2") (pin "48") (pinfunction "P8.4/A21_48") (pintype "bidirectional"))
    )
    (net (code "119") (name "unconnected-(U2-P8.5{slash}A20-Pad49)") (class "Default")
      (node (ref "U2") (pin "49") (pinfunction "P8.5/A20_49") (pintype "bidirectional"))
    )
    (net (code "120") (name "unconnected-(U2-P8.6{slash}A19-Pad50)") (class "Default")
      (node (ref "U2") (pin "50") (pinfunction "P8.6/A19_50") (pintype "bidirectional"))
    )
    (net (code "121") (name "unconnected-(U2-P8.7{slash}A18-Pad51)") (class "Default")
      (node (ref "U2") (pin "51") (pinfunction "P8.7/A18_51") (pintype "bidirectional"))
    )
    (net (code "122") (name "unconnected-(U2-P9.0{slash}A17-Pad52)") (class "Default")
      (node (ref "U2") (pin "52") (pinfunction "P9.0/A17_52") (pintype "bidirectional"))
    )
    (net (code "123") (name "unconnected-(U2-P9.1{slash}A16-Pad53)") (class "Default")
      (node (ref "U2") (pin "53") (pinfunction "P9.1/A16_53") (pintype "bidirectional"))
    )
    (net (code "124") (name "unconnected-(U2-P9.2{slash}TA3.3-Pad74)") (class "Default")
      (node (ref "U2") (pin "74") (pinfunction "P9.2/TA3.3_74") (pintype "bidirectional"))
    )
    (net (code "125") (name "unconnected-(U2-P9.3{slash}TA3.4-Pad75)") (class "Default")
      (node (ref "U2") (pin "75") (pinfunction "P9.3/TA3.4_75") (pintype "bidirectional"))
    )
    (net (code "126") (name "unconnected-(U2-P9.4{slash}UCA3STE-Pad96)") (class "Default")
      (node (ref "U2") (pin "96") (pinfunction "P9.4/UCA3STE_96") (pintype "bidirectional"))
    )
    (net (code "127") (name "unconnected-(U2-P9.5{slash}UCA3CLK-Pad97)") (class "Default")
      (node (ref "U2") (pin "97") (pinfunction "P9.5/UCA3CLK_97") (pintype "bidirectional"))
    )
    (net (code "128") (name "unconnected-(U2-P9.6{slash}UCA3RXD{slash}UCA3SOMI-Pad98)") (class "Default")
      (node (ref "U2") (pin "98") (pinfunction "P9.6/UCA3RXD/UCA3SOMI_98") (pintype "bidirectional"))
    )
    (net (code "129") (name "unconnected-(U2-P9.7{slash}UCA3TXD{slash}UCA3SIMO-Pad99)") (class "Default")
      (node (ref "U2") (pin "99") (pinfunction "P9.7/UCA3TXD/UCA3SIMO_99") (pintype "bidirectional"))
    )
    (net (code "130") (name "unconnected-(U2-P10.0{slash}UCB3STE-Pad100)") (class "Default")
      (node (ref "U2") (pin "100") (pinfunction "P10.0/UCB3STE_100") (pintype "bidirectional"))
    )
    (net (code "131") (name "unconnected-(U2-P10.1{slash}UCB3CLK-Pad1)") (class "Default")
      (node (ref "U2") (pin "1") (pinfunction "P10.1/UCB3CLK_1") (pintype "bidirectional"))
    )
    (net (code "132") (name "unconnected-(U2-P10.2{slash}UCB3SIMO{slash}UCB3SDA-Pad2)") (class "Default")
      (node (ref "U2") (pin "2") (pinfunction "P10.2/UCB3SIMO/UCB3SDA_2") (pintype "bidirectional"))
    )
    (net (code "133") (name "unconnected-(U2-P10.3{slash}UCB3SOMI{slash}UCB3SCL-Pad3)") (class "Default")
      (node (ref "U2") (pin "3") (pinfunction "P10.3/UCB3SOMI/UCB3SCL_3") (pintype "bidirectional"))
    )
    (net (code "134") (name "unconnected-(U2-P10.4{slash}TA3.0{slash}C0.7-Pad24)") (class "Default")
      (node (ref "U2") (pin "24") (pinfunction "P10.4/TA3.0/C0.7_24") (pintype "bidirectional"))
    )
    (net (code "135") (name "unconnected-(U2-P10.5{slash}TA3.1{slash}C0.6-Pad25)") (class "Default")
      (node (ref "U2") (pin "25") (pinfunction "P10.5/TA3.1/C0.6_25") (pintype "bidirectional"))
    )
    (net (code "136") (name "unconnected-(U2-PJ.4{slash}TDI-Pad92)") (class "Default")
      (node (ref "U2") (pin "92") (pinfunction "PJ.4/TDI_92") (pintype "bidirectional"))
    )
  )
)
